# Sensorboard_Schematic.net
KiCad netlist of a schematic drawn in EasyEDA
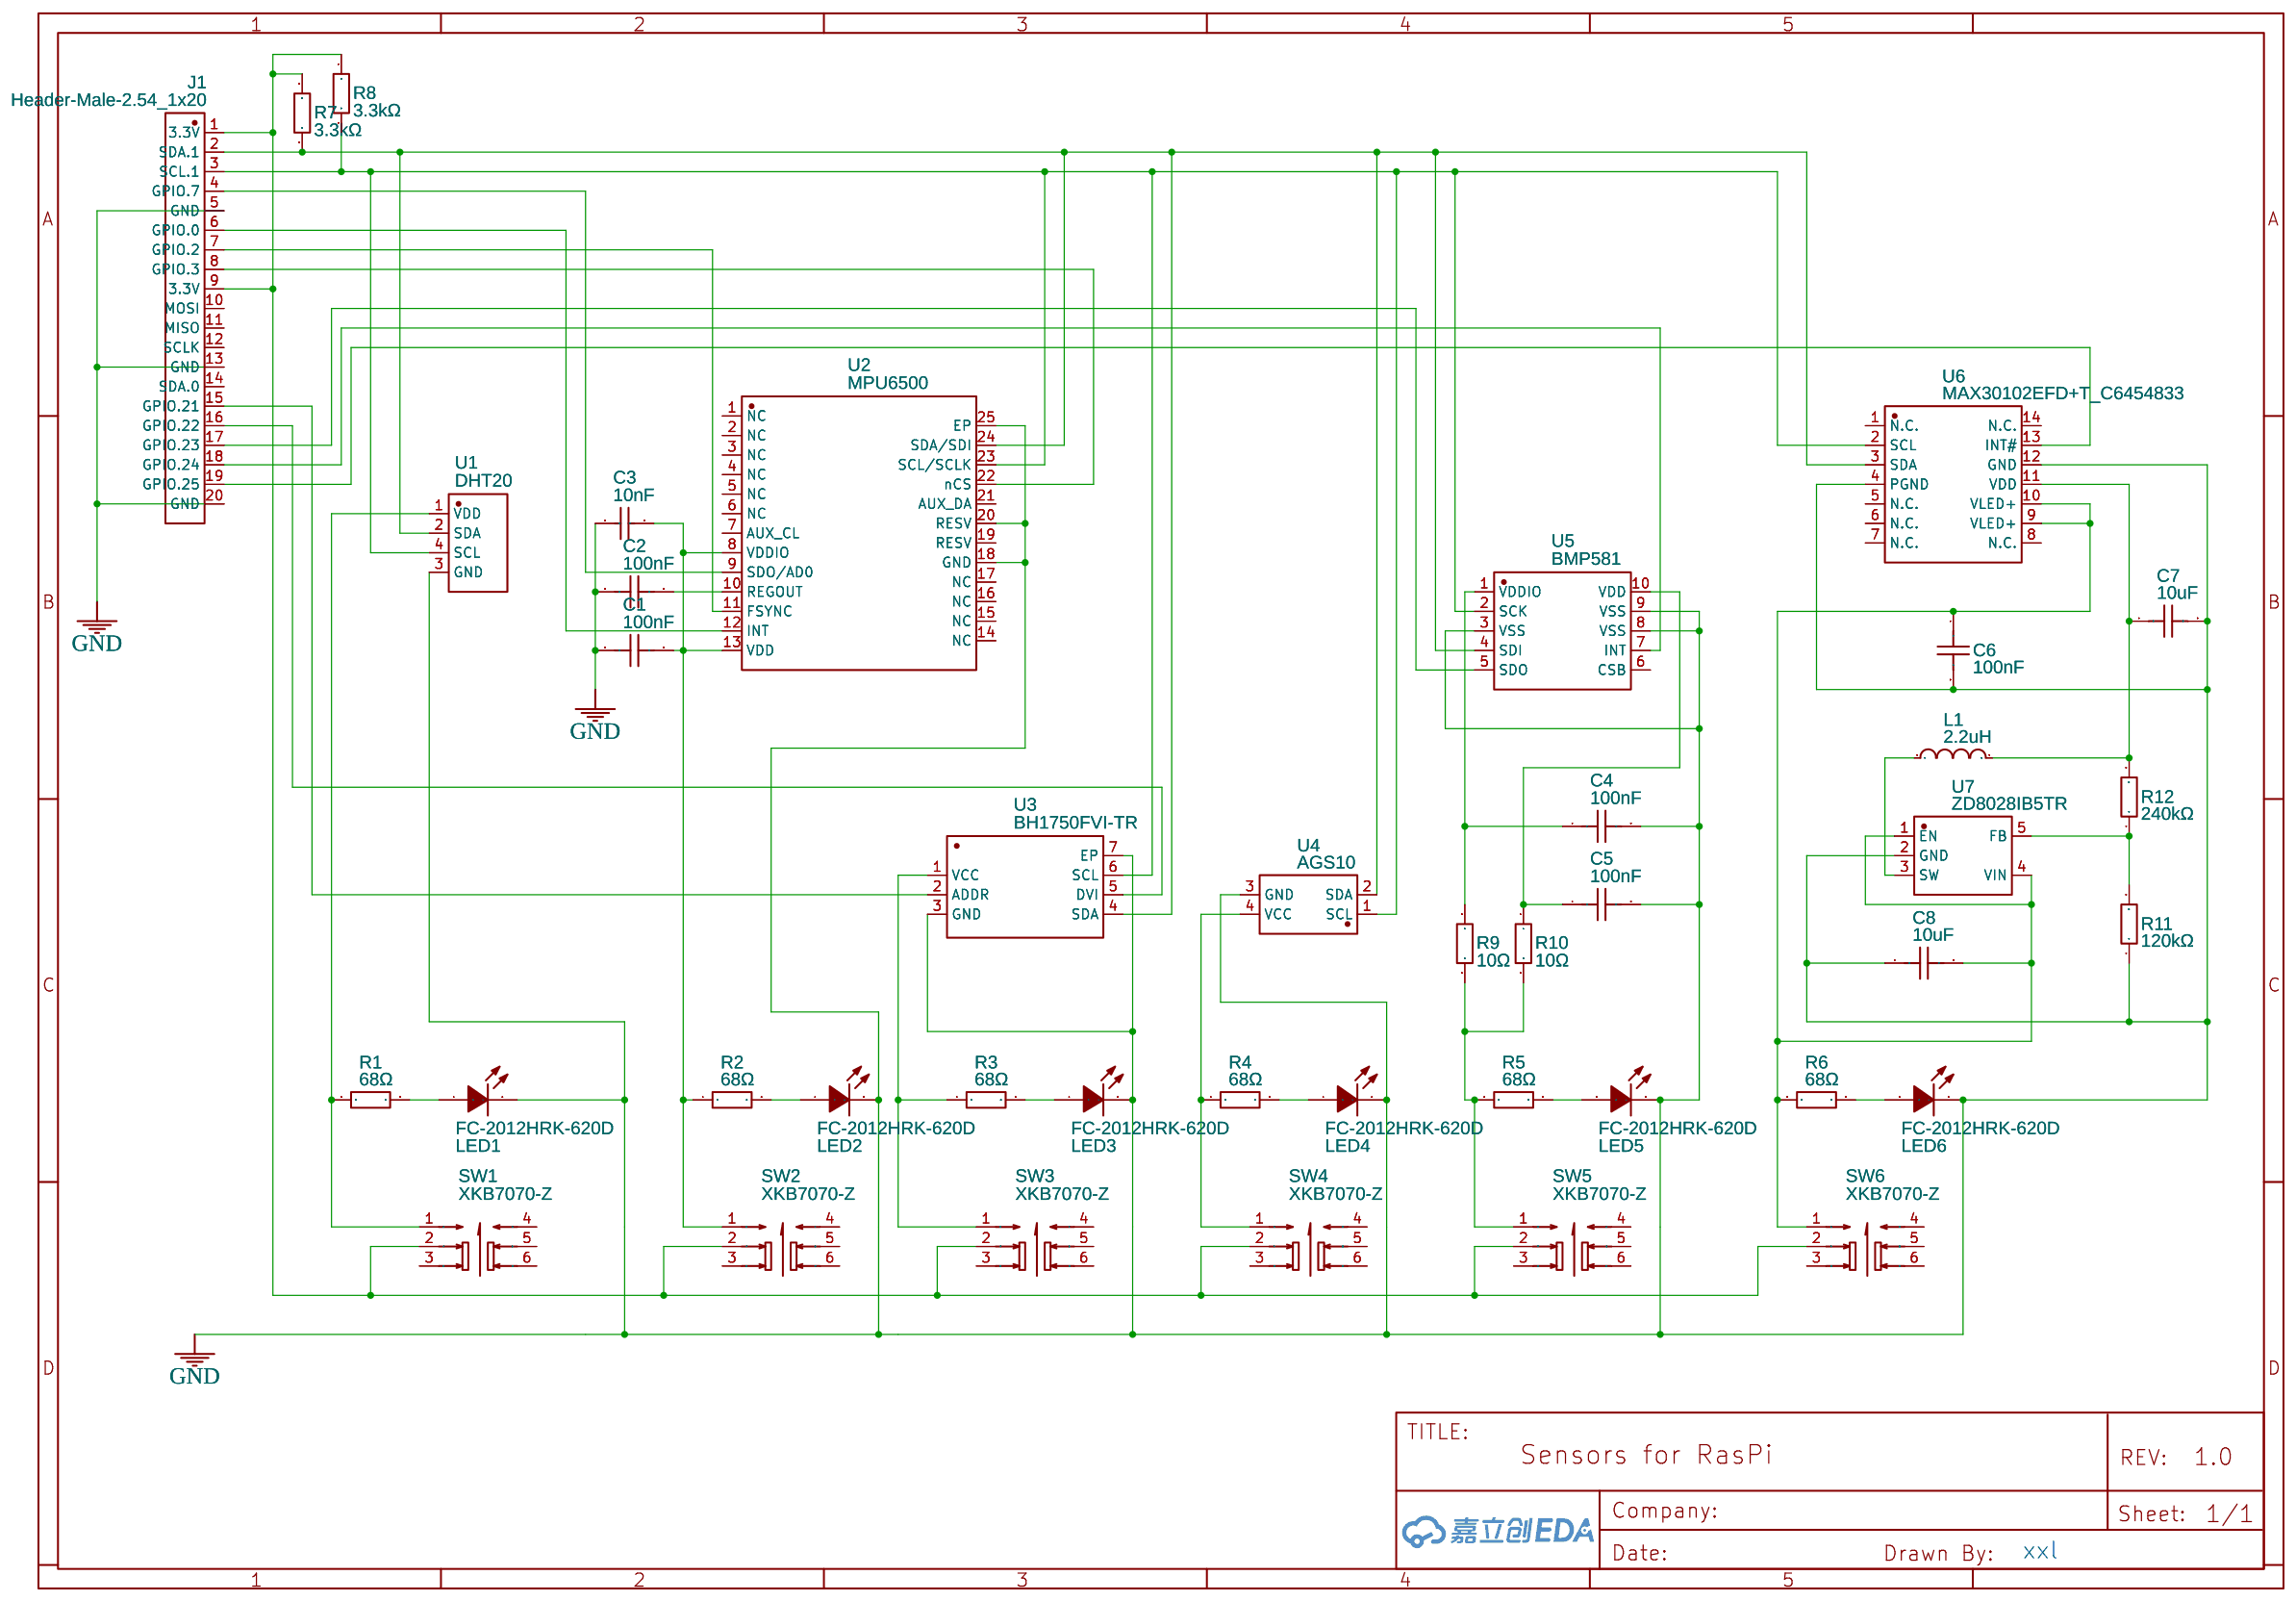
[diagram p0: schematic sheet]

(export (version "E")
  (design (tool "Eeschema 10.0.6"))
  (components
    (comp (ref "C1")
      (value "100nF")
      (fields
        (field (name "Manufacturer Part") "CC0603KRX7R9BB104")
        (field (name "Manufacturer") "YAGEO(国巨)")
      )
      (libsource (lib "") (part "CC0603KRX7R9BB104_1"))
    )
    (comp (ref "C2")
      (value "100nF")
      (fields
        (field (name "Manufacturer Part") "CC0603KRX7R9BB104")
        (field (name "Manufacturer") "YAGEO(国巨)")
      )
      (libsource (lib "") (part "CC0603KRX7R9BB104_1"))
    )
    (comp (ref "C3")
      (value "10nF")
      (fields
        (field (name "Manufacturer Part") "CC0603KRX7R9BB103")
        (field (name "Manufacturer") "YAGEO(国巨)")
      )
      (libsource (lib "") (part "CC0603KRX7R9BB103"))
    )
    (comp (ref "C4")
      (value "100nF")
      (fields
        (field (name "Manufacturer Part") "CC0603KRX7R9BB104")
        (field (name "Manufacturer") "YAGEO(国巨)")
      )
      (libsource (lib "") (part "CC0603KRX7R9BB104_1"))
    )
    (comp (ref "C5")
      (value "100nF")
      (fields
        (field (name "Manufacturer Part") "CC0603KRX7R9BB104")
        (field (name "Manufacturer") "YAGEO(国巨)")
      )
      (libsource (lib "") (part "CC0603KRX7R9BB104_1"))
    )
    (comp (ref "C6")
      (value "100nF")
      (fields
        (field (name "Manufacturer Part") "CC0603KRX7R9BB104")
        (field (name "Manufacturer") "YAGEO(国巨)")
      )
      (libsource (lib "") (part "CC0603KRX7R9BB104"))
    )
    (comp (ref "C7")
      (value "10uF")
      (fields
        (field (name "Manufacturer Part") "CL21A106KAYNNNE")
        (field (name "Manufacturer") "SAMSUNG(三星)")
      )
      (libsource (lib "") (part "CL21A106KAYNNNE"))
    )
    (comp (ref "C8")
      (value "10uF")
      (fields
        (field (name "Manufacturer Part") "CL21A106KAYNNNE")
        (field (name "Manufacturer") "SAMSUNG(三星)")
      )
      (libsource (lib "") (part "CL21A106KAYNNNE"))
    )
    (comp (ref "J1")
      (value "Header-Male-2.54_1x20")
      (fields (field (name "Manufacturer Part") "2.54-1*20P直针") (field (name "Manufacturer") "BOOMELE(博穆精密)"))
      (libsource (lib "") (part "Header-Male-2.54_1x20"))
    )
    (comp (ref "L1")
      (value "2.2uH")
      (fields (field (name "Manufacturer Part") "CMI201209U2R2KT") (field (name "Manufacturer") "FH(风华)"))
      (libsource (lib "") (part "CMI201209U2R2KT"))
    )
    (comp (ref "LED1")
      (value "FC-2012HRK-620D")
      (fields (field (name "Manufacturer Part") "NCD0805R1") (field (name "Manufacturer") "国星光电"))
      (libsource (lib "") (part "FC-2012HRK-620D"))
    )
    (comp (ref "LED2")
      (value "FC-2012HRK-620D")
      (fields (field (name "Manufacturer Part") "NCD0805R1") (field (name "Manufacturer") "国星光电"))
      (libsource (lib "") (part "FC-2012HRK-620D"))
    )
    (comp (ref "LED3")
      (value "FC-2012HRK-620D")
      (fields (field (name "Manufacturer Part") "NCD0805R1") (field (name "Manufacturer") "国星光电"))
      (libsource (lib "") (part "FC-2012HRK-620D"))
    )
    (comp (ref "LED4")
      (value "FC-2012HRK-620D")
      (fields (field (name "Manufacturer Part") "NCD0805R1") (field (name "Manufacturer") "国星光电"))
      (libsource (lib "") (part "FC-2012HRK-620D"))
    )
    (comp (ref "LED5")
      (value "FC-2012HRK-620D")
      (fields (field (name "Manufacturer Part") "NCD0805R1") (field (name "Manufacturer") "国星光电"))
      (libsource (lib "") (part "FC-2012HRK-620D"))
    )
    (comp (ref "LED6")
      (value "FC-2012HRK-620D")
      (fields (field (name "Manufacturer Part") "NCD0805R1") (field (name "Manufacturer") "国星光电"))
      (libsource (lib "") (part "FC-2012HRK-620D"))
    )
    (comp (ref "R1")
      (value "68Ω")
      (fields
        (field (name "Manufacturer Part") "0805W8F680JT5E")
        (field (name "Manufacturer") "UNI-ROYAL(厚声)")
      )
      (libsource (lib "") (part "0805W8F680JT5E"))
    )
    (comp (ref "R2")
      (value "68Ω")
      (fields
        (field (name "Manufacturer Part") "0805W8F680JT5E")
        (field (name "Manufacturer") "UNI-ROYAL(厚声)")
      )
      (libsource (lib "") (part "0805W8F680JT5E"))
    )
    (comp (ref "R3")
      (value "68Ω")
      (fields
        (field (name "Manufacturer Part") "0805W8F680JT5E")
        (field (name "Manufacturer") "UNI-ROYAL(厚声)")
      )
      (libsource (lib "") (part "0805W8F680JT5E"))
    )
    (comp (ref "R4")
      (value "68Ω")
      (fields
        (field (name "Manufacturer Part") "0805W8F680JT5E")
        (field (name "Manufacturer") "UNI-ROYAL(厚声)")
      )
      (libsource (lib "") (part "0805W8F680JT5E"))
    )
    (comp (ref "R5")
      (value "68Ω")
      (fields
        (field (name "Manufacturer Part") "0805W8F680JT5E")
        (field (name "Manufacturer") "UNI-ROYAL(厚声)")
      )
      (libsource (lib "") (part "0805W8F680JT5E"))
    )
    (comp (ref "R6")
      (value "68Ω")
      (fields
        (field (name "Manufacturer Part") "0805W8F680JT5E")
        (field (name "Manufacturer") "UNI-ROYAL(厚声)")
      )
      (libsource (lib "") (part "0805W8F680JT5E"))
    )
    (comp (ref "R7")
      (value "3.3kΩ")
      (fields
        (field (name "Manufacturer Part") "0603WAF3301T5E")
        (field (name "Manufacturer") "UNI-ROYAL(厚声)")
      )
      (libsource (lib "") (part "0603WAF3301T5E"))
    )
    (comp (ref "R8")
      (value "3.3kΩ")
      (fields
        (field (name "Manufacturer Part") "0603WAF3301T5E")
        (field (name "Manufacturer") "UNI-ROYAL(厚声)")
      )
      (libsource (lib "") (part "0603WAF3301T5E_1"))
    )
    (comp (ref "R9")
      (value "10Ω")
      (fields
        (field (name "Manufacturer Part") "0603WAF100JT5E")
        (field (name "Manufacturer") "UNI-ROYAL(厚声)")
      )
      (libsource (lib "") (part "0603WAF100JT5E"))
    )
    (comp (ref "R10")
      (value "10Ω")
      (fields
        (field (name "Manufacturer Part") "0603WAF100JT5E")
        (field (name "Manufacturer") "UNI-ROYAL(厚声)")
      )
      (libsource (lib "") (part "0603WAF100JT5E_1"))
    )
    (comp (ref "R11")
      (value "120kΩ")
      (fields
        (field (name "Manufacturer Part") "0603WAF1203T5E")
        (field (name "Manufacturer") "UNI-ROYAL(厚声)")
      )
      (libsource (lib "") (part "0603WAF1203T5E"))
    )
    (comp (ref "R12")
      (value "240kΩ")
      (fields
        (field (name "Manufacturer Part") "0603WAF2403T5E")
        (field (name "Manufacturer") "UNI-ROYAL(厚声)")
      )
      (libsource (lib "") (part "0603WAF2403T5E"))
    )
    (comp (ref "SW1")
      (value "XKB7070-Z")
      (fields (field (name "Manufacturer") "XKB Connectivity(中国星坤)"))
      (libsource (lib "") (part "XKB7070-Z"))
    )
    (comp (ref "SW2")
      (value "XKB7070-Z")
      (fields (field (name "Manufacturer") "XKB Connectivity(中国星坤)"))
      (libsource (lib "") (part "XKB7070-Z"))
    )
    (comp (ref "SW3")
      (value "XKB7070-Z")
      (fields (field (name "Manufacturer") "XKB Connectivity(中国星坤)"))
      (libsource (lib "") (part "XKB7070-Z"))
    )
    (comp (ref "SW4")
      (value "XKB7070-Z")
      (fields (field (name "Manufacturer") "XKB Connectivity(中国星坤)"))
      (libsource (lib "") (part "XKB7070-Z"))
    )
    (comp (ref "SW5")
      (value "XKB7070-Z")
      (fields (field (name "Manufacturer") "XKB Connectivity(中国星坤)"))
      (libsource (lib "") (part "XKB7070-Z"))
    )
    (comp (ref "SW6")
      (value "XKB7070-Z")
      (fields (field (name "Manufacturer") "XKB Connectivity(中国星坤)"))
      (libsource (lib "") (part "XKB7070-Z"))
    )
    (comp (ref "U1")
      (value "DHT20")
      (fields (field (name "Manufacturer") "广州奥松"))
      (libsource (lib "") (part "DHT20"))
    )
    (comp (ref "U2")
      (value "MPU6500")
      (fields
        (field (name "Manufacturer Part") "MPU-6500")
        (field (name "Manufacturer") "TDK InvenSense(应美盛)")
      )
      (libsource (lib "") (part "MPU6500"))
    )
    (comp (ref "U3")
      (value "BH1750FVI-TR")
      (fields (field (name "Manufacturer") "ROHM(罗姆)"))
      (libsource (lib "") (part "BH1750FVI-TR"))
    )
    (comp (ref "U4")
      (value "AGS10")
      (fields (field (name "Manufacturer") "广州奥松"))
      (libsource (lib "") (part "AGS10"))
    )
    (comp (ref "U5")
      (value "BMP581")
      (fields (field (name "Manufacturer") "Bosch(博世)"))
      (libsource (lib "") (part "BMP581"))
    )
    (comp (ref "U6")
      (value "MAX30102EFD+T_C6454833")
      (fields
        (field (name "Manufacturer Part") "MAX30102EFD+T")
        (field (name "Manufacturer") "ADI(亚德诺)/MAXIM(美信)")
      )
      (libsource (lib "") (part "MAX30102EFD+T_C6454833"))
    )
    (comp (ref "U7")
      (value "ZD8028IB5TR")
      (fields (field (name "Manufacturer") "Zetta(澜智)"))
      (libsource (lib "") (part "ZD8028IB5TR"))
    )
  )
  (nets
    (net (code "1") (name "GND") (class "Default")
      (node (ref "C1") (pin "1") (pinfunction "1_1") (pintype "unspecified"))
      (node (ref "C2") (pin "1") (pinfunction "1_1") (pintype "unspecified"))
      (node (ref "C3") (pin "1") (pinfunction "1_1") (pintype "input"))
      (node (ref "C4") (pin "2") (pinfunction "2_2") (pintype "unspecified"))
      (node (ref "C5") (pin "2") (pinfunction "2_2") (pintype "unspecified"))
      (node (ref "C6") (pin "2") (pinfunction "2_2") (pintype "unspecified"))
      (node (ref "C7") (pin "2") (pinfunction "2_2") (pintype "unspecified"))
      (node (ref "C8") (pin "1") (pinfunction "1_1") (pintype "unspecified"))
      (node (ref "J1") (pin "13") (pinfunction "GND_13") (pintype "unspecified"))
      (node (ref "J1") (pin "20") (pinfunction "GND_20") (pintype "unspecified"))
      (node (ref "J1") (pin "5") (pinfunction "GND_5") (pintype "unspecified"))
      (node (ref "LED1") (pin "2") (pinfunction "-_2") (pintype "unspecified"))
      (node (ref "LED2") (pin "2") (pinfunction "-_2") (pintype "unspecified"))
      (node (ref "LED3") (pin "2") (pinfunction "-_2") (pintype "unspecified"))
      (node (ref "LED4") (pin "2") (pinfunction "-_2") (pintype "unspecified"))
      (node (ref "LED5") (pin "2") (pinfunction "-_2") (pintype "unspecified"))
      (node (ref "LED6") (pin "2") (pinfunction "-_2") (pintype "unspecified"))
      (node (ref "R11") (pin "1") (pinfunction "1_1") (pintype "input"))
      (node (ref "U1") (pin "3") (pinfunction "GND_3") (pintype "unspecified"))
      (node (ref "U2") (pin "18") (pinfunction "GND_18") (pintype "unspecified"))
      (node (ref "U2") (pin "20") (pinfunction "RESV_20") (pintype "unspecified"))
      (node (ref "U2") (pin "25") (pinfunction "EP_25") (pintype "unspecified"))
      (node (ref "U3") (pin "3") (pinfunction "GND_3") (pintype "unspecified"))
      (node (ref "U3") (pin "7") (pinfunction "EP_7") (pintype "unspecified"))
      (node (ref "U4") (pin "3") (pinfunction "GND_3") (pintype "unspecified"))
      (node (ref "U5") (pin "3") (pinfunction "VSS_3") (pintype "unspecified"))
      (node (ref "U5") (pin "8") (pinfunction "VSS_8") (pintype "unspecified"))
      (node (ref "U5") (pin "9") (pinfunction "VSS_9") (pintype "unspecified"))
      (node (ref "U6") (pin "12") (pinfunction "GND_12") (pintype "unspecified"))
      (node (ref "U6") (pin "4") (pinfunction "PGND_4") (pintype "unspecified"))
      (node (ref "U7") (pin "2") (pinfunction "GND_2") (pintype "unspecified"))
    )
    (net (code "2") (name "Net-(J1-3.3V-Pad1)") (class "Default")
      (node (ref "J1") (pin "1") (pinfunction "3.3V_1") (pintype "unspecified"))
      (node (ref "J1") (pin "9") (pinfunction "3.3V_9") (pintype "unspecified"))
      (node (ref "R7") (pin "2") (pinfunction "2_2") (pintype "input"))
      (node (ref "R8") (pin "1") (pinfunction "1_1") (pintype "input"))
      (node (ref "SW1") (pin "2") (pinfunction "2_2") (pintype "unspecified"))
      (node (ref "SW2") (pin "2") (pinfunction "2_2") (pintype "unspecified"))
      (node (ref "SW3") (pin "2") (pinfunction "2_2") (pintype "unspecified"))
      (node (ref "SW4") (pin "2") (pinfunction "2_2") (pintype "unspecified"))
      (node (ref "SW5") (pin "2") (pinfunction "2_2") (pintype "unspecified"))
      (node (ref "SW6") (pin "2") (pinfunction "2_2") (pintype "unspecified"))
    )
    (net (code "3") (name "Net-(J1-GPIO.0)") (class "Default")
      (node (ref "J1") (pin "6") (pinfunction "GPIO.0_6") (pintype "unspecified"))
      (node (ref "U2") (pin "12") (pinfunction "INT_12") (pintype "unspecified"))
    )
    (net (code "4") (name "Net-(J1-GPIO.2)") (class "Default")
      (node (ref "J1") (pin "7") (pinfunction "GPIO.2_7") (pintype "unspecified"))
      (node (ref "U2") (pin "11") (pinfunction "FSYNC_11") (pintype "unspecified"))
    )
    (net (code "5") (name "Net-(J1-GPIO.3)") (class "Default")
      (node (ref "J1") (pin "8") (pinfunction "GPIO.3_8") (pintype "unspecified"))
      (node (ref "U2") (pin "22") (pinfunction "nCS_22") (pintype "unspecified"))
    )
    (net (code "6") (name "Net-(J1-GPIO.7)") (class "Default")
      (node (ref "J1") (pin "4") (pinfunction "GPIO.7_4") (pintype "unspecified"))
      (node (ref "U2") (pin "9") (pinfunction "SDO/AD0_9") (pintype "unspecified"))
    )
    (net (code "7") (name "Net-(J1-GPIO.21)") (class "Default")
      (node (ref "J1") (pin "15") (pinfunction "GPIO.21_15") (pintype "unspecified"))
      (node (ref "U3") (pin "2") (pinfunction "ADDR_2") (pintype "unspecified"))
    )
    (net (code "8") (name "Net-(J1-GPIO.22)") (class "Default")
      (node (ref "J1") (pin "16") (pinfunction "GPIO.22_16") (pintype "unspecified"))
      (node (ref "U3") (pin "5") (pinfunction "DVI_5") (pintype "unspecified"))
    )
    (net (code "9") (name "Net-(J1-GPIO.23)") (class "Default")
      (node (ref "J1") (pin "17") (pinfunction "GPIO.23_17") (pintype "unspecified"))
      (node (ref "U5") (pin "5") (pinfunction "SDO_5") (pintype "unspecified"))
    )
    (net (code "10") (name "Net-(J1-GPIO.24)") (class "Default")
      (node (ref "J1") (pin "18") (pinfunction "GPIO.24_18") (pintype "unspecified"))
      (node (ref "U5") (pin "7") (pinfunction "INT_7") (pintype "unspecified"))
    )
    (net (code "11") (name "Net-(J1-GPIO.25)") (class "Default")
      (node (ref "J1") (pin "19") (pinfunction "GPIO.25_19") (pintype "unspecified"))
      (node (ref "U6") (pin "13") (pinfunction "INT#_13") (pintype "unspecified"))
    )
    (net (code "12") (name "Net-(J1-SCL.1)") (class "Default")
      (node (ref "J1") (pin "3") (pinfunction "SCL.1_3") (pintype "unspecified"))
      (node (ref "R8") (pin "2") (pinfunction "2_2") (pintype "input"))
      (node (ref "U1") (pin "4") (pinfunction "SCL_4") (pintype "unspecified"))
      (node (ref "U2") (pin "23") (pinfunction "SCL/SCLK_23") (pintype "unspecified"))
      (node (ref "U3") (pin "6") (pinfunction "SCL_6") (pintype "unspecified"))
      (node (ref "U4") (pin "1") (pinfunction "SCL_1") (pintype "unspecified"))
      (node (ref "U5") (pin "2") (pinfunction "SCK_2") (pintype "unspecified"))
      (node (ref "U6") (pin "2") (pinfunction "SCL_2") (pintype "unspecified"))
    )
    (net (code "13") (name "Net-(J1-SDA.1)") (class "Default")
      (node (ref "J1") (pin "2") (pinfunction "SDA.1_2") (pintype "unspecified"))
      (node (ref "R7") (pin "1") (pinfunction "1_1") (pintype "input"))
      (node (ref "U1") (pin "2") (pinfunction "SDA_2") (pintype "unspecified"))
      (node (ref "U2") (pin "24") (pinfunction "SDA/SDI_24") (pintype "unspecified"))
      (node (ref "U3") (pin "4") (pinfunction "SDA_4") (pintype "unspecified"))
      (node (ref "U4") (pin "2") (pinfunction "SDA_2") (pintype "unspecified"))
      (node (ref "U5") (pin "4") (pinfunction "SDI_4") (pintype "unspecified"))
      (node (ref "U6") (pin "3") (pinfunction "SDA_3") (pintype "unspecified"))
    )
    (net (code "14") (name "Net-(LED1-+)") (class "Default")
      (node (ref "LED1") (pin "1") (pinfunction "+_1") (pintype "unspecified"))
      (node (ref "R1") (pin "2") (pinfunction "2_2") (pintype "input"))
    )
    (net (code "15") (name "Net-(LED2-+)") (class "Default")
      (node (ref "LED2") (pin "1") (pinfunction "+_1") (pintype "unspecified"))
      (node (ref "R2") (pin "2") (pinfunction "2_2") (pintype "input"))
    )
    (net (code "16") (name "Net-(LED3-+)") (class "Default")
      (node (ref "LED3") (pin "1") (pinfunction "+_1") (pintype "unspecified"))
      (node (ref "R3") (pin "2") (pinfunction "2_2") (pintype "input"))
    )
    (net (code "17") (name "Net-(LED4-+)") (class "Default")
      (node (ref "LED4") (pin "1") (pinfunction "+_1") (pintype "unspecified"))
      (node (ref "R4") (pin "2") (pinfunction "2_2") (pintype "input"))
    )
    (net (code "18") (name "Net-(LED5-+)") (class "Default")
      (node (ref "LED5") (pin "1") (pinfunction "+_1") (pintype "unspecified"))
      (node (ref "R5") (pin "2") (pinfunction "2_2") (pintype "input"))
    )
    (net (code "19") (name "Net-(LED6-+)") (class "Default")
      (node (ref "LED6") (pin "1") (pinfunction "+_1") (pintype "unspecified"))
      (node (ref "R6") (pin "2") (pinfunction "2_2") (pintype "input"))
    )
    (net (code "20") (name "Net-(R10-Pad2)") (class "Default")
      (node (ref "R10") (pin "2") (pinfunction "2_2") (pintype "input"))
      (node (ref "R5") (pin "1") (pinfunction "1_1") (pintype "input"))
      (node (ref "R9") (pin "1") (pinfunction "1_1") (pintype "input"))
      (node (ref "SW5") (pin "1") (pinfunction "1_1") (pintype "unspecified"))
    )
    (net (code "21") (name "Net-(U1-VDD)") (class "Default")
      (node (ref "R1") (pin "1") (pinfunction "1_1") (pintype "input"))
      (node (ref "SW1") (pin "1") (pinfunction "1_1") (pintype "unspecified"))
      (node (ref "U1") (pin "1") (pinfunction "VDD_1") (pintype "unspecified"))
    )
    (net (code "22") (name "Net-(U2-REGOUT)") (class "Default")
      (node (ref "C2") (pin "2") (pinfunction "2_2") (pintype "unspecified"))
      (node (ref "U2") (pin "10") (pinfunction "REGOUT_10") (pintype "unspecified"))
    )
    (net (code "23") (name "Net-(U2-VDD)") (class "Default")
      (node (ref "C1") (pin "2") (pinfunction "2_2") (pintype "unspecified"))
      (node (ref "C3") (pin "2") (pinfunction "2_2") (pintype "input"))
      (node (ref "R2") (pin "1") (pinfunction "1_1") (pintype "input"))
      (node (ref "SW2") (pin "1") (pinfunction "1_1") (pintype "unspecified"))
      (node (ref "U2") (pin "13") (pinfunction "VDD_13") (pintype "unspecified"))
      (node (ref "U2") (pin "8") (pinfunction "VDDIO_8") (pintype "unspecified"))
    )
    (net (code "24") (name "Net-(U3-VCC)") (class "Default")
      (node (ref "R3") (pin "1") (pinfunction "1_1") (pintype "input"))
      (node (ref "SW3") (pin "1") (pinfunction "1_1") (pintype "unspecified"))
      (node (ref "U3") (pin "1") (pinfunction "VCC_1") (pintype "unspecified"))
    )
    (net (code "25") (name "Net-(U4-VCC)") (class "Default")
      (node (ref "R4") (pin "1") (pinfunction "1_1") (pintype "input"))
      (node (ref "SW4") (pin "1") (pinfunction "1_1") (pintype "unspecified"))
      (node (ref "U4") (pin "4") (pinfunction "VCC_4") (pintype "unspecified"))
    )
    (net (code "26") (name "Net-(U5-VDD)") (class "Default")
      (node (ref "C5") (pin "1") (pinfunction "1_1") (pintype "unspecified"))
      (node (ref "R10") (pin "1") (pinfunction "1_1") (pintype "input"))
      (node (ref "U5") (pin "10") (pinfunction "VDD_10") (pintype "unspecified"))
    )
    (net (code "27") (name "Net-(U5-VDDIO)") (class "Default")
      (node (ref "C4") (pin "1") (pinfunction "1_1") (pintype "unspecified"))
      (node (ref "R9") (pin "2") (pinfunction "2_2") (pintype "input"))
      (node (ref "U5") (pin "1") (pinfunction "VDDIO_1") (pintype "unspecified"))
    )
    (net (code "28") (name "Net-(U6-VDD)") (class "Default")
      (node (ref "C7") (pin "1") (pinfunction "1_1") (pintype "unspecified"))
      (node (ref "L1") (pin "2") (pinfunction "2_2") (pintype "unspecified"))
      (node (ref "R12") (pin "2") (pinfunction "2_2") (pintype "input"))
      (node (ref "U6") (pin "11") (pinfunction "VDD_11") (pintype "unspecified"))
    )
    (net (code "29") (name "Net-(U7-EN)") (class "Default")
      (node (ref "C6") (pin "1") (pinfunction "1_1") (pintype "unspecified"))
      (node (ref "C8") (pin "2") (pinfunction "2_2") (pintype "unspecified"))
      (node (ref "R6") (pin "1") (pinfunction "1_1") (pintype "input"))
      (node (ref "SW6") (pin "1") (pinfunction "1_1") (pintype "unspecified"))
      (node (ref "U6") (pin "10") (pinfunction "VLED+_10") (pintype "unspecified"))
      (node (ref "U6") (pin "9") (pinfunction "VLED+_9") (pintype "unspecified"))
      (node (ref "U7") (pin "1") (pinfunction "EN_1") (pintype "unspecified"))
      (node (ref "U7") (pin "4") (pinfunction "VIN_4") (pintype "unspecified"))
    )
    (net (code "30") (name "Net-(U7-FB)") (class "Default")
      (node (ref "R11") (pin "2") (pinfunction "2_2") (pintype "input"))
      (node (ref "R12") (pin "1") (pinfunction "1_1") (pintype "input"))
      (node (ref "U7") (pin "5") (pinfunction "FB_5") (pintype "unspecified"))
    )
    (net (code "31") (name "Net-(U7-SW)") (class "Default")
      (node (ref "L1") (pin "1") (pinfunction "1_1") (pintype "unspecified"))
      (node (ref "U7") (pin "3") (pinfunction "SW_3") (pintype "unspecified"))
    )
    (net (code "32") (name "unconnected-(J1-MISO-Pad11)") (class "Default")
      (node (ref "J1") (pin "11") (pinfunction "MISO_11") (pintype "unspecified"))
    )
    (net (code "33") (name "unconnected-(J1-MOSI-Pad10)") (class "Default")
      (node (ref "J1") (pin "10") (pinfunction "MOSI_10") (pintype "unspecified"))
    )
    (net (code "34") (name "unconnected-(J1-SCLK-Pad12)") (class "Default")
      (node (ref "J1") (pin "12") (pinfunction "SCLK_12") (pintype "unspecified"))
    )
    (net (code "35") (name "unconnected-(J1-SDA.0-Pad14)") (class "Default")
      (node (ref "J1") (pin "14") (pinfunction "SDA.0_14") (pintype "unspecified"))
    )
    (net (code "36") (name "unconnected-(SW1-Pad3)") (class "Default")
      (node (ref "SW1") (pin "3") (pinfunction "3_3") (pintype "unspecified"))
    )
    (net (code "37") (name "unconnected-(SW1-Pad4)") (class "Default")
      (node (ref "SW1") (pin "4") (pinfunction "4_4") (pintype "unspecified"))
    )
    (net (code "38") (name "unconnected-(SW1-Pad5)") (class "Default")
      (node (ref "SW1") (pin "5") (pinfunction "5_5") (pintype "unspecified"))
    )
    (net (code "39") (name "unconnected-(SW1-Pad6)") (class "Default")
      (node (ref "SW1") (pin "6") (pinfunction "6_6") (pintype "unspecified"))
    )
    (net (code "40") (name "unconnected-(SW2-Pad3)") (class "Default")
      (node (ref "SW2") (pin "3") (pinfunction "3_3") (pintype "unspecified"))
    )
    (net (code "41") (name "unconnected-(SW2-Pad4)") (class "Default")
      (node (ref "SW2") (pin "4") (pinfunction "4_4") (pintype "unspecified"))
    )
    (net (code "42") (name "unconnected-(SW2-Pad5)") (class "Default")
      (node (ref "SW2") (pin "5") (pinfunction "5_5") (pintype "unspecified"))
    )
    (net (code "43") (name "unconnected-(SW2-Pad6)") (class "Default")
      (node (ref "SW2") (pin "6") (pinfunction "6_6") (pintype "unspecified"))
    )
    (net (code "44") (name "unconnected-(SW3-Pad3)") (class "Default")
      (node (ref "SW3") (pin "3") (pinfunction "3_3") (pintype "unspecified"))
    )
    (net (code "45") (name "unconnected-(SW3-Pad4)") (class "Default")
      (node (ref "SW3") (pin "4") (pinfunction "4_4") (pintype "unspecified"))
    )
    (net (code "46") (name "unconnected-(SW3-Pad5)") (class "Default")
      (node (ref "SW3") (pin "5") (pinfunction "5_5") (pintype "unspecified"))
    )
    (net (code "47") (name "unconnected-(SW3-Pad6)") (class "Default")
      (node (ref "SW3") (pin "6") (pinfunction "6_6") (pintype "unspecified"))
    )
    (net (code "48") (name "unconnected-(SW4-Pad3)") (class "Default")
      (node (ref "SW4") (pin "3") (pinfunction "3_3") (pintype "unspecified"))
    )
    (net (code "49") (name "unconnected-(SW4-Pad4)") (class "Default")
      (node (ref "SW4") (pin "4") (pinfunction "4_4") (pintype "unspecified"))
    )
    (net (code "50") (name "unconnected-(SW4-Pad5)") (class "Default")
      (node (ref "SW4") (pin "5") (pinfunction "5_5") (pintype "unspecified"))
    )
    (net (code "51") (name "unconnected-(SW4-Pad6)") (class "Default")
      (node (ref "SW4") (pin "6") (pinfunction "6_6") (pintype "unspecified"))
    )
    (net (code "52") (name "unconnected-(SW5-Pad3)") (class "Default")
      (node (ref "SW5") (pin "3") (pinfunction "3_3") (pintype "unspecified"))
    )
    (net (code "53") (name "unconnected-(SW5-Pad4)") (class "Default")
      (node (ref "SW5") (pin "4") (pinfunction "4_4") (pintype "unspecified"))
    )
    (net (code "54") (name "unconnected-(SW5-Pad5)") (class "Default")
      (node (ref "SW5") (pin "5") (pinfunction "5_5") (pintype "unspecified"))
    )
    (net (code "55") (name "unconnected-(SW5-Pad6)") (class "Default")
      (node (ref "SW5") (pin "6") (pinfunction "6_6") (pintype "unspecified"))
    )
    (net (code "56") (name "unconnected-(SW6-Pad3)") (class "Default")
      (node (ref "SW6") (pin "3") (pinfunction "3_3") (pintype "unspecified"))
    )
    (net (code "57") (name "unconnected-(SW6-Pad4)") (class "Default")
      (node (ref "SW6") (pin "4") (pinfunction "4_4") (pintype "unspecified"))
    )
    (net (code "58") (name "unconnected-(SW6-Pad5)") (class "Default")
      (node (ref "SW6") (pin "5") (pinfunction "5_5") (pintype "unspecified"))
    )
    (net (code "59") (name "unconnected-(SW6-Pad6)") (class "Default")
      (node (ref "SW6") (pin "6") (pinfunction "6_6") (pintype "unspecified"))
    )
    (net (code "60") (name "unconnected-(U2-AUX_CL-Pad7)") (class "Default")
      (node (ref "U2") (pin "7") (pinfunction "AUX_CL_7") (pintype "unspecified"))
    )
    (net (code "61") (name "unconnected-(U2-AUX_DA-Pad21)") (class "Default")
      (node (ref "U2") (pin "21") (pinfunction "AUX_DA_21") (pintype "unspecified"))
    )
    (net (code "62") (name "unconnected-(U2-NC-Pad1)") (class "Default")
      (node (ref "U2") (pin "1") (pinfunction "NC_1") (pintype "unspecified"))
    )
    (net (code "63") (name "unconnected-(U2-NC-Pad2)") (class "Default")
      (node (ref "U2") (pin "2") (pinfunction "NC_2") (pintype "unspecified"))
    )
    (net (code "64") (name "unconnected-(U2-NC-Pad3)") (class "Default")
      (node (ref "U2") (pin "3") (pinfunction "NC_3") (pintype "unspecified"))
    )
    (net (code "65") (name "unconnected-(U2-NC-Pad4)") (class "Default")
      (node (ref "U2") (pin "4") (pinfunction "NC_4") (pintype "unspecified"))
    )
    (net (code "66") (name "unconnected-(U2-NC-Pad5)") (class "Default")
      (node (ref "U2") (pin "5") (pinfunction "NC_5") (pintype "unspecified"))
    )
    (net (code "67") (name "unconnected-(U2-NC-Pad6)") (class "Default")
      (node (ref "U2") (pin "6") (pinfunction "NC_6") (pintype "unspecified"))
    )
    (net (code "68") (name "unconnected-(U2-NC-Pad14)") (class "Default")
      (node (ref "U2") (pin "14") (pinfunction "NC_14") (pintype "unspecified"))
    )
    (net (code "69") (name "unconnected-(U2-NC-Pad15)") (class "Default")
      (node (ref "U2") (pin "15") (pinfunction "NC_15") (pintype "unspecified"))
    )
    (net (code "70") (name "unconnected-(U2-NC-Pad16)") (class "Default")
      (node (ref "U2") (pin "16") (pinfunction "NC_16") (pintype "unspecified"))
    )
    (net (code "71") (name "unconnected-(U2-NC-Pad17)") (class "Default")
      (node (ref "U2") (pin "17") (pinfunction "NC_17") (pintype "unspecified"))
    )
    (net (code "72") (name "unconnected-(U2-RESV-Pad19)") (class "Default")
      (node (ref "U2") (pin "19") (pinfunction "RESV_19") (pintype "unspecified"))
    )
    (net (code "73") (name "unconnected-(U5-CSB-Pad6)") (class "Default")
      (node (ref "U5") (pin "6") (pinfunction "CSB_6") (pintype "unspecified"))
    )
    (net (code "74") (name "unconnected-(U6-N.C.-Pad1)") (class "Default")
      (node (ref "U6") (pin "1") (pinfunction "N.C._1") (pintype "unspecified"))
    )
    (net (code "75") (name "unconnected-(U6-N.C.-Pad5)") (class "Default")
      (node (ref "U6") (pin "5") (pinfunction "N.C._5") (pintype "unspecified"))
    )
    (net (code "76") (name "unconnected-(U6-N.C.-Pad6)") (class "Default")
      (node (ref "U6") (pin "6") (pinfunction "N.C._6") (pintype "unspecified"))
    )
    (net (code "77") (name "unconnected-(U6-N.C.-Pad7)") (class "Default")
      (node (ref "U6") (pin "7") (pinfunction "N.C._7") (pintype "unspecified"))
    )
    (net (code "78") (name "unconnected-(U6-N.C.-Pad8)") (class "Default")
      (node (ref "U6") (pin "8") (pinfunction "N.C._8") (pintype "unspecified"))
    )
    (net (code "79") (name "unconnected-(U6-N.C.-Pad14)") (class "Default")
      (node (ref "U6") (pin "14") (pinfunction "N.C._14") (pintype "unspecified"))
    )
  )
)
